# G008X.net
KiCad netlist of a schematic drawn in EAGLE
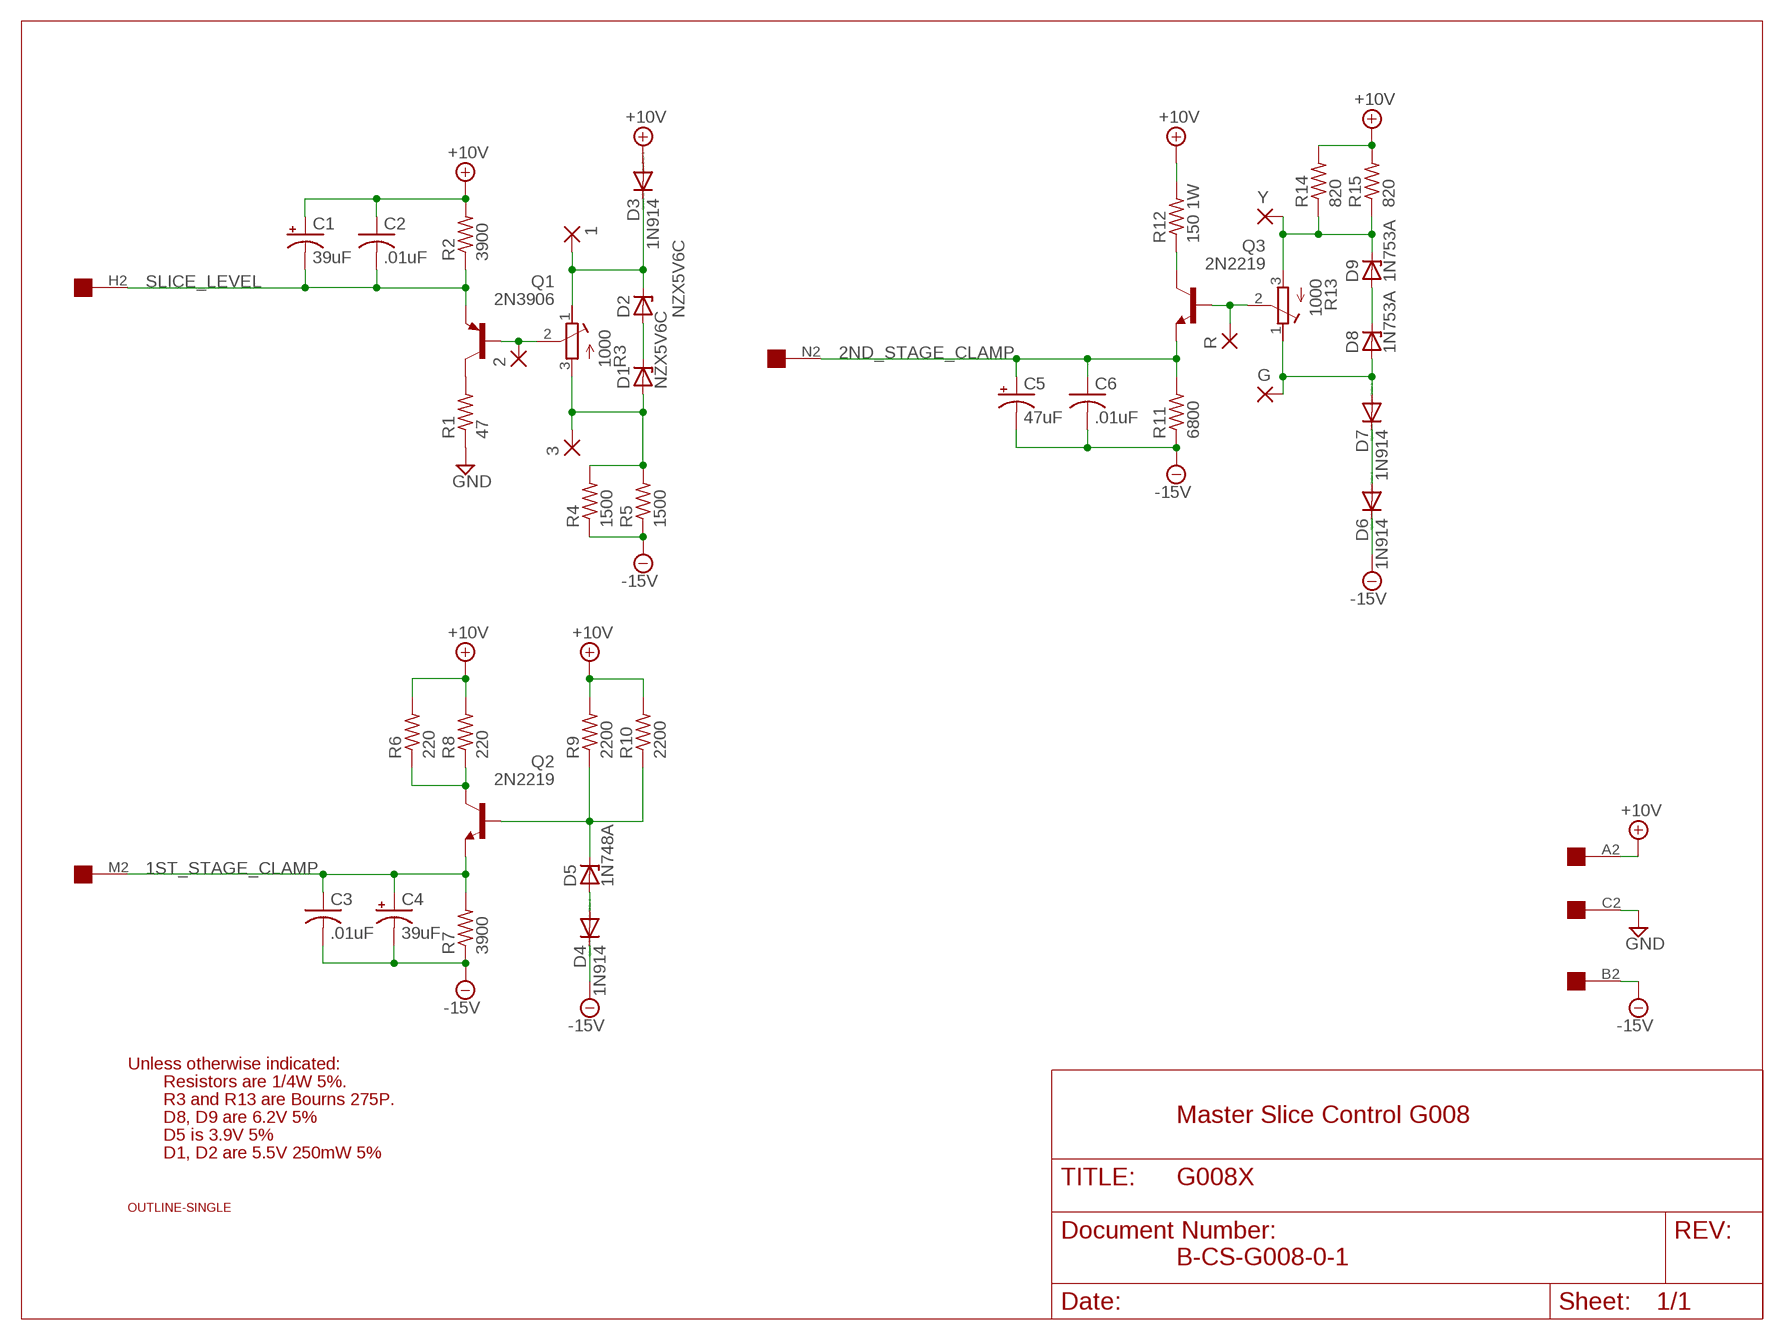
[diagram p0: schematic, sheet 1]

(export (version "E")
  (design (tool "Eeschema 10.0.6"))
  (components
    (comp (ref "1")
      (value "2,54/0,8")
      (footprint "eagle-import:2,54_0,8")
      (libsource (lib "eagle-import") (part "2,54/0,8"))
    )
    (comp (ref "2")
      (value "2,54/0,8")
      (footprint "eagle-import:2,54_0,8")
      (libsource (lib "eagle-import") (part "2,54/0,8"))
    )
    (comp (ref "3")
      (value "2,54/0,8")
      (footprint "eagle-import:2,54_0,8")
      (libsource (lib "eagle-import") (part "2,54/0,8"))
    )
    (comp (ref "C1")
      (value "39uF")
      (footprint "eagle-import:E15-5")
      (libsource (lib "eagle-import") (part "CPOL-USE15-5AXIAL"))
    )
    (comp (ref "C2")
      (value ".01uF")
      (footprint "eagle-import:C050-025X075")
      (libsource (lib "eagle-import") (part "C-US050-025X075"))
    )
    (comp (ref "C3")
      (value ".01uF")
      (footprint "eagle-import:C050-025X075")
      (libsource (lib "eagle-import") (part "C-US050-025X075"))
    )
    (comp (ref "C4")
      (value "39uF")
      (footprint "eagle-import:E15-5")
      (libsource (lib "eagle-import") (part "CPOL-USE15-5AXIAL"))
    )
    (comp (ref "C5")
      (value "47uF")
      (footprint "eagle-import:E22-6")
      (libsource (lib "eagle-import") (part "CPOL-USE22-6AXIAL"))
    )
    (comp (ref "C6")
      (value ".01uF")
      (footprint "eagle-import:C050-025X075")
      (libsource (lib "eagle-import") (part "C-US050-025X075"))
    )
    (comp (ref "D1")
      (value "NZX5V6C")
      (footprint "eagle-import:DO35Z10")
      (libsource (lib "eagle-import") (part "ZENER-DIODEDO35Z10"))
    )
    (comp (ref "D2")
      (value "NZX5V6C")
      (footprint "eagle-import:DO35Z10")
      (libsource (lib "eagle-import") (part "ZENER-DIODEDO35Z10"))
    )
    (comp (ref "D3")
      (value "1N914")
      (footprint "eagle-import:DO35-10")
      (libsource (lib "eagle-import") (part "1N4148DO35-10"))
    )
    (comp (ref "D4")
      (value "1N914")
      (footprint "eagle-import:DO35-10")
      (libsource (lib "eagle-import") (part "1N4148DO35-10"))
    )
    (comp (ref "D5")
      (value "1N748A")
      (footprint "eagle-import:DO35Z10")
      (libsource (lib "eagle-import") (part "ZENER-DIODEDO35Z10"))
    )
    (comp (ref "D6")
      (value "1N914")
      (footprint "eagle-import:DO35-10")
      (libsource (lib "eagle-import") (part "1N4148DO35-10"))
    )
    (comp (ref "D7")
      (value "1N914")
      (footprint "eagle-import:DO35-10")
      (libsource (lib "eagle-import") (part "1N4148DO35-10"))
    )
    (comp (ref "D8")
      (value "1N753A")
      (footprint "eagle-import:DO35Z10")
      (libsource (lib "eagle-import") (part "ZENER-DIODEDO35Z10"))
    )
    (comp (ref "D9")
      (value "1N753A")
      (footprint "eagle-import:DO35Z10")
      (libsource (lib "eagle-import") (part "ZENER-DIODEDO35Z10"))
    )
    (comp (ref "G")
      (value "2,54/0,8")
      (footprint "eagle-import:2,54_0,8")
      (libsource (lib "eagle-import") (part "2,54/0,8"))
    )
    (comp (ref "Q1")
      (value "2N3906")
      (footprint "eagle-import:TO39")
      (libsource (lib "eagle-import") (part "2N2904"))
    )
    (comp (ref "Q2")
      (value "2N2219")
      (footprint "eagle-import:TO5")
      (libsource (lib "eagle-import") (part "2N2102"))
    )
    (comp (ref "Q3")
      (value "2N2219")
      (footprint "eagle-import:TO5")
      (libsource (lib "eagle-import") (part "2N2102"))
    )
    (comp (ref "R")
      (value "2,54/0,8")
      (footprint "eagle-import:2,54_0,8")
      (libsource (lib "eagle-import") (part "2,54/0,8"))
    )
    (comp (ref "R1")
      (value "47")
      (footprint "eagle-import:0207_10")
      (libsource (lib "eagle-import") (part "R-US_0207/10"))
    )
    (comp (ref "R2")
      (value "3900")
      (footprint "eagle-import:0207_10")
      (libsource (lib "eagle-import") (part "R-US_0207/10"))
    )
    (comp (ref "R3")
      (value "1000")
      (footprint "eagle-import:3006Y")
      (libsource (lib "eagle-import") (part "275P"))
    )
    (comp (ref "R4")
      (value "1500")
      (footprint "eagle-import:0207_10")
      (libsource (lib "eagle-import") (part "R-US_0207/10"))
    )
    (comp (ref "R5")
      (value "1500")
      (footprint "eagle-import:0207_10")
      (libsource (lib "eagle-import") (part "R-US_0207/10"))
    )
    (comp (ref "R6")
      (value "220")
      (footprint "eagle-import:0207_10")
      (libsource (lib "eagle-import") (part "R-US_0207/10"))
    )
    (comp (ref "R7")
      (value "3900")
      (footprint "eagle-import:0207_10")
      (libsource (lib "eagle-import") (part "R-US_0207/10"))
    )
    (comp (ref "R8")
      (value "220")
      (footprint "eagle-import:0207_10")
      (libsource (lib "eagle-import") (part "R-US_0207/10"))
    )
    (comp (ref "R9")
      (value "2200")
      (footprint "eagle-import:0207_10")
      (libsource (lib "eagle-import") (part "R-US_0207/10"))
    )
    (comp (ref "R10")
      (value "2200")
      (footprint "eagle-import:0207_10")
      (libsource (lib "eagle-import") (part "R-US_0207/10"))
    )
    (comp (ref "R11")
      (value "6800")
      (footprint "eagle-import:0207_10")
      (libsource (lib "eagle-import") (part "R-US_0207/10"))
    )
    (comp (ref "R12")
      (value "150 1W")
      (footprint "eagle-import:0617_22")
      (libsource (lib "eagle-import") (part "R-US_0617/22"))
    )
    (comp (ref "R13")
      (value "1000")
      (footprint "eagle-import:3006Y")
      (libsource (lib "eagle-import") (part "275P"))
    )
    (comp (ref "R14")
      (value "820")
      (footprint "eagle-import:0207_10")
      (libsource (lib "eagle-import") (part "R-US_0207/10"))
    )
    (comp (ref "R15")
      (value "820")
      (footprint "eagle-import:0207_10")
      (libsource (lib "eagle-import") (part "R-US_0207/10"))
    )
    (comp (ref "U$1")
      (value "OUTLINE-SINGLE")
      (footprint "eagle-import:SINGLE")
      (libsource (lib "eagle-import") (part "OUTLINE-SINGLE"))
    )
    (comp (ref "U$2")
      (value "EDGE-1")
      (footprint "eagle-import:EDGE-CON1")
      (libsource (lib "eagle-import") (part "EDGE-1"))
    )
    (comp (ref "Y")
      (value "2,54/0,8")
      (footprint "eagle-import:2,54_0,8")
      (libsource (lib "eagle-import") (part "2,54/0,8"))
    )
  )
  (nets
    (net (code "1") (name "+10V") (class "Default")
      (node (ref "C1") (pin "+") (pinfunction "+_+") (pintype "passive"))
      (node (ref "C2") (pin "1") (pinfunction "1_1") (pintype "passive"))
      (node (ref "D3") (pin "A") (pinfunction "A_A") (pintype "passive"))
      (node (ref "R10") (pin "2") (pinfunction "2_2") (pintype "passive"))
      (node (ref "R12") (pin "2") (pinfunction "2_2") (pintype "passive"))
      (node (ref "R14") (pin "2") (pinfunction "2_2") (pintype "passive"))
      (node (ref "R15") (pin "2") (pinfunction "2_2") (pintype "passive"))
      (node (ref "R2") (pin "2") (pinfunction "2_2") (pintype "passive"))
      (node (ref "R6") (pin "2") (pinfunction "2_2") (pintype "passive"))
      (node (ref "R8") (pin "2") (pinfunction "2_2") (pintype "passive"))
      (node (ref "R9") (pin "2") (pinfunction "2_2") (pintype "passive"))
      (node (ref "U$2") (pin "A2") (pinfunction "1_A2") (pintype "bidirectional"))
    )
    (net (code "2") (name "-15V") (class "Default")
      (node (ref "C3") (pin "2") (pinfunction "2_2") (pintype "passive"))
      (node (ref "C4") (pin "-") (pinfunction "-_-") (pintype "passive"))
      (node (ref "C5") (pin "-") (pinfunction "-_-") (pintype "passive"))
      (node (ref "C6") (pin "2") (pinfunction "2_2") (pintype "passive"))
      (node (ref "D4") (pin "C") (pinfunction "C_C") (pintype "passive"))
      (node (ref "D6") (pin "C") (pinfunction "C_C") (pintype "passive"))
      (node (ref "R11") (pin "1") (pinfunction "1_1") (pintype "passive"))
      (node (ref "R4") (pin "1") (pinfunction "1_1") (pintype "passive"))
      (node (ref "R5") (pin "1") (pinfunction "1_1") (pintype "passive"))
      (node (ref "R7") (pin "1") (pinfunction "1_1") (pintype "passive"))
      (node (ref "U$2") (pin "B2") (pinfunction "1_B2") (pintype "bidirectional"))
    )
    (net (code "3") (name "/1ST_STAGE_CLAMP") (class "Default")
      (node (ref "C3") (pin "1") (pinfunction "1_1") (pintype "passive"))
      (node (ref "C4") (pin "+") (pinfunction "+_+") (pintype "passive"))
      (node (ref "Q2") (pin "1") (pinfunction "E_1") (pintype "passive"))
      (node (ref "R7") (pin "2") (pinfunction "2_2") (pintype "passive"))
      (node (ref "U$2") (pin "M2") (pinfunction "1_M2") (pintype "bidirectional"))
    )
    (net (code "4") (name "/2ND_STAGE_CLAMP") (class "Default")
      (node (ref "C5") (pin "+") (pinfunction "+_+") (pintype "passive"))
      (node (ref "C6") (pin "1") (pinfunction "1_1") (pintype "passive"))
      (node (ref "Q3") (pin "1") (pinfunction "E_1") (pintype "passive"))
      (node (ref "R11") (pin "2") (pinfunction "2_2") (pintype "passive"))
      (node (ref "U$2") (pin "N2") (pinfunction "1_N2") (pintype "bidirectional"))
    )
    (net (code "5") (name "/SLICE_LEVEL") (class "Default")
      (node (ref "C1") (pin "-") (pinfunction "-_-") (pintype "passive"))
      (node (ref "C2") (pin "2") (pinfunction "2_2") (pintype "passive"))
      (node (ref "Q1") (pin "1") (pinfunction "E_1") (pintype "passive"))
      (node (ref "R2") (pin "1") (pinfunction "1_1") (pintype "passive"))
      (node (ref "U$2") (pin "H2") (pinfunction "1_H2") (pintype "bidirectional"))
    )
    (net (code "6") (name "GND") (class "Default")
      (node (ref "R1") (pin "1") (pinfunction "1_1") (pintype "passive"))
      (node (ref "U$2") (pin "C2") (pinfunction "1_C2") (pintype "bidirectional"))
    )
    (net (code "7") (name "Net-(1-P)") (class "Default")
      (node (ref "1") (pin "1") (pinfunction "P_1") (pintype "passive"))
      (node (ref "D2") (pin "C") (pinfunction "C_C") (pintype "passive"))
      (node (ref "D3") (pin "C") (pinfunction "C_C") (pintype "passive"))
      (node (ref "R3") (pin "1") (pinfunction "A_1") (pintype "passive"))
    )
    (net (code "8") (name "Net-(2-P)") (class "Default")
      (node (ref "2") (pin "1") (pinfunction "P_1") (pintype "passive"))
      (node (ref "Q1") (pin "2") (pinfunction "B_2") (pintype "passive"))
      (node (ref "R3") (pin "2") (pinfunction "S_2") (pintype "passive"))
    )
    (net (code "9") (name "Net-(3-P)") (class "Default")
      (node (ref "3") (pin "1") (pinfunction "P_1") (pintype "passive"))
      (node (ref "D1") (pin "A") (pinfunction "A_A") (pintype "passive"))
      (node (ref "R3") (pin "3") (pinfunction "E_3") (pintype "passive"))
      (node (ref "R4") (pin "2") (pinfunction "2_2") (pintype "passive"))
      (node (ref "R5") (pin "2") (pinfunction "2_2") (pintype "passive"))
    )
    (net (code "10") (name "Net-(D1-PadC)") (class "Default")
      (node (ref "D1") (pin "C") (pinfunction "C_C") (pintype "passive"))
      (node (ref "D2") (pin "A") (pinfunction "A_A") (pintype "passive"))
    )
    (net (code "11") (name "Net-(D4-PadA)") (class "Default")
      (node (ref "D4") (pin "A") (pinfunction "A_A") (pintype "passive"))
      (node (ref "D5") (pin "A") (pinfunction "A_A") (pintype "passive"))
    )
    (net (code "12") (name "Net-(D6-PadA)") (class "Default")
      (node (ref "D6") (pin "A") (pinfunction "A_A") (pintype "passive"))
      (node (ref "D7") (pin "C") (pinfunction "C_C") (pintype "passive"))
    )
    (net (code "13") (name "Net-(D8-PadC)") (class "Default")
      (node (ref "D8") (pin "C") (pinfunction "C_C") (pintype "passive"))
      (node (ref "D9") (pin "A") (pinfunction "A_A") (pintype "passive"))
    )
    (net (code "14") (name "Net-(G-P)") (class "Default")
      (node (ref "D7") (pin "A") (pinfunction "A_A") (pintype "passive"))
      (node (ref "D8") (pin "A") (pinfunction "A_A") (pintype "passive"))
      (node (ref "G") (pin "1") (pinfunction "P_1") (pintype "passive"))
      (node (ref "R13") (pin "1") (pinfunction "A_1") (pintype "passive"))
    )
    (net (code "15") (name "Net-(Q1-C)") (class "Default")
      (node (ref "Q1") (pin "3") (pinfunction "C_3") (pintype "passive"))
      (node (ref "R1") (pin "2") (pinfunction "2_2") (pintype "passive"))
    )
    (net (code "16") (name "Net-(Q2-B)") (class "Default")
      (node (ref "D5") (pin "C") (pinfunction "C_C") (pintype "passive"))
      (node (ref "Q2") (pin "2") (pinfunction "B_2") (pintype "passive"))
      (node (ref "R10") (pin "1") (pinfunction "1_1") (pintype "passive"))
      (node (ref "R9") (pin "1") (pinfunction "1_1") (pintype "passive"))
    )
    (net (code "17") (name "Net-(Q2-C)") (class "Default")
      (node (ref "Q2") (pin "3") (pinfunction "C_3") (pintype "passive"))
      (node (ref "R6") (pin "1") (pinfunction "1_1") (pintype "passive"))
      (node (ref "R8") (pin "1") (pinfunction "1_1") (pintype "passive"))
    )
    (net (code "18") (name "Net-(Q3-B)") (class "Default")
      (node (ref "Q3") (pin "2") (pinfunction "B_2") (pintype "passive"))
      (node (ref "R") (pin "1") (pinfunction "P_1") (pintype "passive"))
      (node (ref "R13") (pin "2") (pinfunction "S_2") (pintype "passive"))
    )
    (net (code "19") (name "Net-(Q3-C)") (class "Default")
      (node (ref "Q3") (pin "3") (pinfunction "C_3") (pintype "passive"))
      (node (ref "R12") (pin "1") (pinfunction "1_1") (pintype "passive"))
    )
    (net (code "20") (name "Net-(R13-E)") (class "Default")
      (node (ref "D9") (pin "C") (pinfunction "C_C") (pintype "passive"))
      (node (ref "R13") (pin "3") (pinfunction "E_3") (pintype "passive"))
      (node (ref "R14") (pin "1") (pinfunction "1_1") (pintype "passive"))
      (node (ref "R15") (pin "1") (pinfunction "1_1") (pintype "passive"))
      (node (ref "Y") (pin "1") (pinfunction "P_1") (pintype "passive"))
    )
  )
)
